# 1_-Power_Pins_Page_of_RK3399.net
KiCad netlist of a schematic drawn in Altium Designer
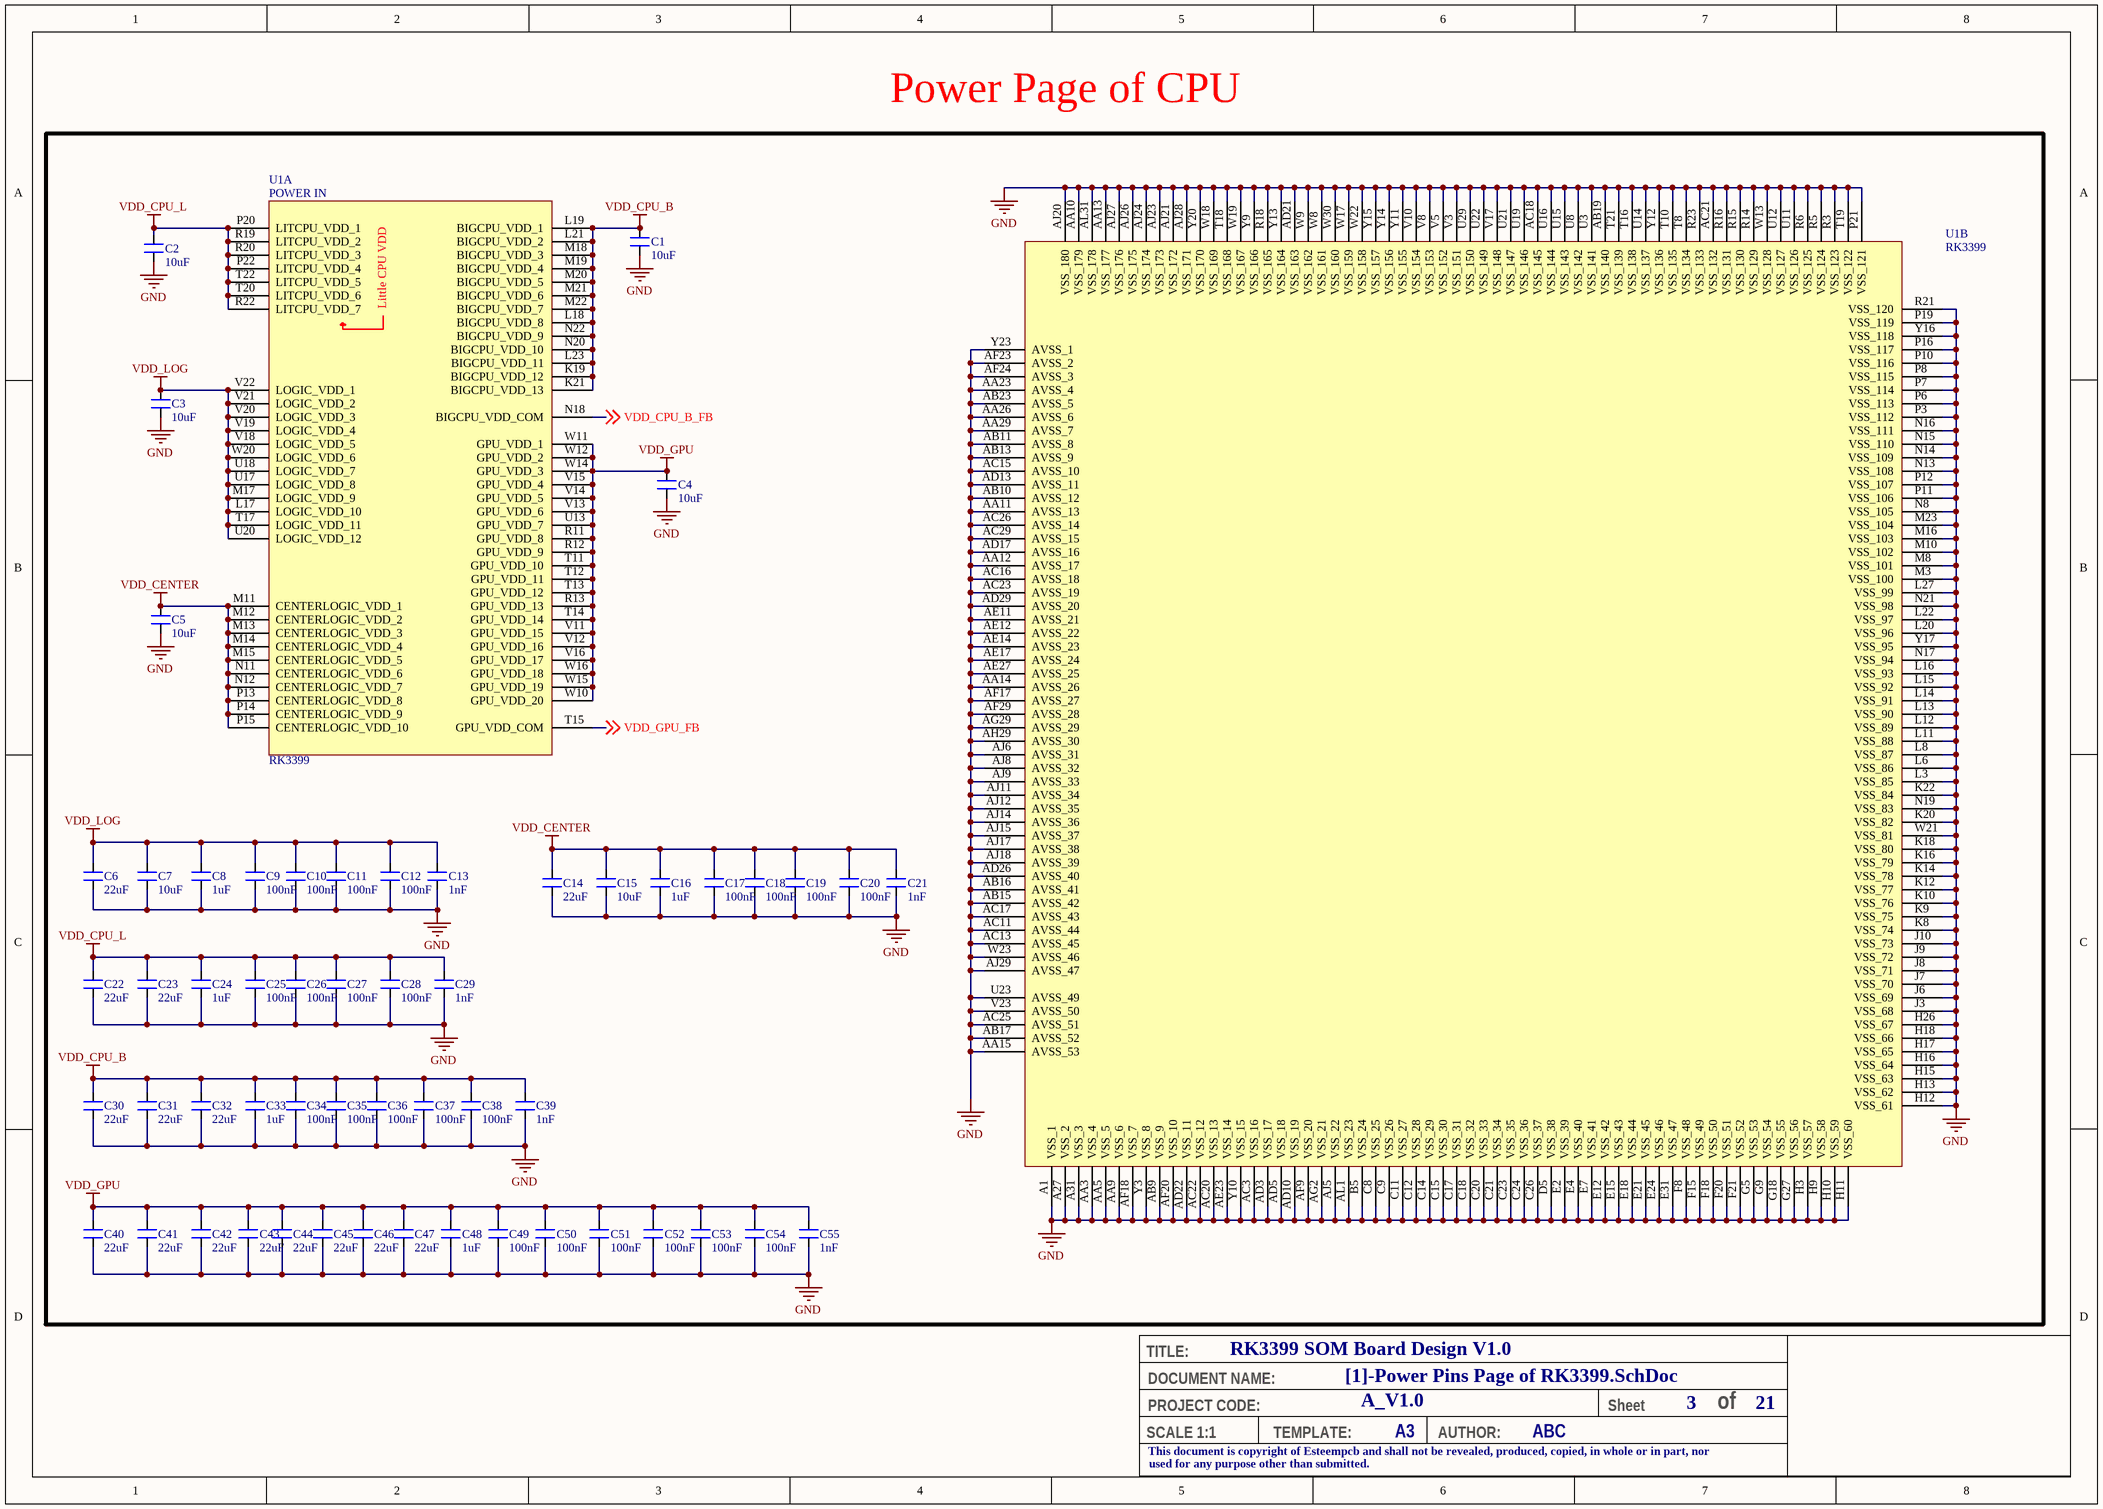
[diagram p0: [1]-Power Pins Page of RK3399.SchDoc]

(export (version "E")
  (design (tool "Eeschema 10.0.6"))
  (components
    (comp (ref "C1")
      (value "10uF")
      (footprint "CAP_0402")
      (description "10µF ±20% 10V Ceramic Capacitor X5R 0402 (1005 Metric)")
      (fields
        (field (name "MANUFACTURER PART NUMBER") "CL05A106MP5NUNC")
        (field (name "MANUFACTURER") "Samsung Electro-Mechanics")
      )
      (libsource (lib "RK3399 _Module_Schlib") (part "CAP_10uF-10V-20%-0402"))
    )
    (comp (ref "C2")
      (value "10uF")
      (footprint "CAP_0402")
      (description "10µF ±20% 10V Ceramic Capacitor X5R 0402 (1005 Metric)")
      (fields
        (field (name "MANUFACTURER PART NUMBER") "CL05A106MP5NUNC")
        (field (name "MANUFACTURER") "Samsung Electro-Mechanics")
      )
      (libsource (lib "RK3399 _Module_Schlib") (part "CAP_10uF-10V-20%-0402"))
    )
    (comp (ref "C3")
      (value "10uF")
      (footprint "CAP_0402")
      (description "10µF ±20% 10V Ceramic Capacitor X5R 0402 (1005 Metric)")
      (fields
        (field (name "MANUFACTURER PART NUMBER") "CL05A106MP5NUNC")
        (field (name "MANUFACTURER") "Samsung Electro-Mechanics")
      )
      (libsource (lib "RK3399 _Module_Schlib") (part "CAP_10uF-10V-20%-0402"))
    )
    (comp (ref "C4")
      (value "10uF")
      (footprint "CAP_0402")
      (description "10µF ±20% 10V Ceramic Capacitor X5R 0402 (1005 Metric)")
      (fields
        (field (name "MANUFACTURER PART NUMBER") "CL05A106MP5NUNC")
        (field (name "MANUFACTURER") "Samsung Electro-Mechanics")
      )
      (libsource (lib "RK3399 _Module_Schlib") (part "CAP_10uF-10V-20%-0402"))
    )
    (comp (ref "C5")
      (value "10uF")
      (footprint "CAP_0402")
      (description "10µF ±20% 10V Ceramic Capacitor X5R 0402 (1005 Metric)")
      (fields
        (field (name "MANUFACTURER PART NUMBER") "CL05A106MP5NUNC")
        (field (name "MANUFACTURER") "Samsung Electro-Mechanics")
      )
      (libsource (lib "RK3399 _Module_Schlib") (part "CAP_10uF-10V-20%-0402"))
    )
    (comp (ref "C6")
      (value "22uF")
      (footprint "CAP_0402")
      (description "22µF ±20% 6.3V Ceramic Capacitor X5R 0402 (1005 Metric)")
      (fields
        (field (name "MANUFACTURER") "Murata Electronics")
        (field (name "MANUFACTURER PART NUMBER") "CL05A226MQ5N6J8")
      )
      (libsource (lib "RK3399 _Module_Intlib") (part "CAP_22uF-6.3V-20%-0402"))
    )
    (comp (ref "C7")
      (value "10uF")
      (footprint "CAP_0402")
      (description "10µF ±20% 10V Ceramic Capacitor X5R 0402 (1005 Metric)")
      (fields
        (field (name "MANUFACTURER PART NUMBER") "CL05A106MP5NUNC")
        (field (name "MANUFACTURER") "Samsung Electro-Mechanics")
      )
      (libsource (lib "RK3399 _Module_Schlib") (part "CAP_10uF-10V-20%-0402"))
    )
    (comp (ref "C8")
      (value "1uF")
      (footprint "CAP_0201")
      (description "1µF ±20% 16V Ceramic Capacitor X5R 0201 (0603 Metric)")
      (fields
        (field (name "MANUFACTURER") "Samsung Electro-Mechanics")
        (field (name "MANUFACTURER PART NUMBER") "CL03A105MO3NRNH")
      )
      (libsource (lib "RK3399 _Module_Intlib") (part "CAP_1uF-16V-10%-0201"))
    )
    (comp (ref "C9")
      (value "100nF")
      (footprint "CAP_0201")
      (description "0.1µF ±10% 25V Ceramic Capacitor X5R 0201 (0603 Metric)")
      (fields
        (field (name "MANUFACTURER") "TDK Corporation")
        (field (name "MANUFACTURER PART NUMBER") "C0603X5R1E104K030BB")
      )
      (libsource (lib "RK3399 _Module_Intlib") (part "CAP_100nF-25V-10%-0201"))
    )
    (comp (ref "C10")
      (value "100nF")
      (footprint "CAP_0201")
      (description "0.1µF ±10% 25V Ceramic Capacitor X5R 0201 (0603 Metric)")
      (fields
        (field (name "MANUFACTURER") "TDK Corporation")
        (field (name "MANUFACTURER PART NUMBER") "C0603X5R1E104K030BB")
      )
      (libsource (lib "RK3399 _Module_Intlib") (part "CAP_100nF-25V-10%-0201"))
    )
    (comp (ref "C11")
      (value "100nF")
      (footprint "CAP_0201")
      (description "0.1µF ±10% 25V Ceramic Capacitor X5R 0201 (0603 Metric)")
      (fields
        (field (name "MANUFACTURER") "TDK Corporation")
        (field (name "MANUFACTURER PART NUMBER") "C0603X5R1E104K030BB")
      )
      (libsource (lib "RK3399 _Module_Intlib") (part "CAP_100nF-25V-10%-0201"))
    )
    (comp (ref "C12")
      (value "100nF")
      (footprint "CAP_0201")
      (description "0.1µF ±10% 25V Ceramic Capacitor X5R 0201 (0603 Metric)")
      (fields
        (field (name "MANUFACTURER") "TDK Corporation")
        (field (name "MANUFACTURER PART NUMBER") "C0603X5R1E104K030BB")
      )
      (libsource (lib "RK3399 _Module_Intlib") (part "CAP_100nF-25V-10%-0201"))
    )
    (comp (ref "C13")
      (value "1nF")
      (footprint "CAP_0201")
      (description "1000pF ±10% 16V Ceramic Capacitor X7R 0201 (0603 Metric)")
      (fields
        (field (name "MANUFACTURER") "Murata Electronics")
        (field (name "MANUFACTURER PART NUMBER") "GRM033R71C102KA01D")
      )
      (libsource (lib "RK3399 _Module_Intlib") (part "CAP_1nF-16V-10%-0201"))
    )
    (comp (ref "C14")
      (value "22uF")
      (footprint "CAP_0402")
      (description "22µF ±20% 6.3V Ceramic Capacitor X5R 0402 (1005 Metric)")
      (fields
        (field (name "MANUFACTURER") "Murata Electronics")
        (field (name "MANUFACTURER PART NUMBER") "CL05A226MQ5N6J8")
      )
      (libsource (lib "RK3399 _Module_Intlib") (part "CAP_22uF-6.3V-20%-0402"))
    )
    (comp (ref "C15")
      (value "10uF")
      (footprint "CAP_0402")
      (description "10µF ±20% 10V Ceramic Capacitor X5R 0402 (1005 Metric)")
      (fields
        (field (name "MANUFACTURER PART NUMBER") "CL05A106MP5NUNC")
        (field (name "MANUFACTURER") "Samsung Electro-Mechanics")
      )
      (libsource (lib "RK3399 _Module_Schlib") (part "CAP_10uF-10V-20%-0402"))
    )
    (comp (ref "C16")
      (value "1uF")
      (footprint "CAP_0201")
      (description "1µF ±20% 16V Ceramic Capacitor X5R 0201 (0603 Metric)")
      (fields
        (field (name "MANUFACTURER") "Samsung Electro-Mechanics")
        (field (name "MANUFACTURER PART NUMBER") "CL03A105MO3NRNH")
      )
      (libsource (lib "RK3399 _Module_Intlib") (part "CAP_1uF-16V-10%-0201"))
    )
    (comp (ref "C17")
      (value "100nF")
      (footprint "CAP_0201")
      (description "0.1µF ±10% 25V Ceramic Capacitor X5R 0201 (0603 Metric)")
      (fields
        (field (name "MANUFACTURER") "TDK Corporation")
        (field (name "MANUFACTURER PART NUMBER") "C0603X5R1E104K030BB")
      )
      (libsource (lib "RK3399 _Module_Intlib") (part "CAP_100nF-25V-10%-0201"))
    )
    (comp (ref "C18")
      (value "100nF")
      (footprint "CAP_0201")
      (description "0.1µF ±10% 25V Ceramic Capacitor X5R 0201 (0603 Metric)")
      (fields
        (field (name "MANUFACTURER") "TDK Corporation")
        (field (name "MANUFACTURER PART NUMBER") "C0603X5R1E104K030BB")
      )
      (libsource (lib "RK3399 _Module_Intlib") (part "CAP_100nF-25V-10%-0201"))
    )
    (comp (ref "C19")
      (value "100nF")
      (footprint "CAP_0201")
      (description "0.1µF ±10% 25V Ceramic Capacitor X5R 0201 (0603 Metric)")
      (fields
        (field (name "MANUFACTURER") "TDK Corporation")
        (field (name "MANUFACTURER PART NUMBER") "C0603X5R1E104K030BB")
      )
      (libsource (lib "RK3399 _Module_Intlib") (part "CAP_100nF-25V-10%-0201"))
    )
    (comp (ref "C20")
      (value "100nF")
      (footprint "CAP_0201")
      (description "0.1µF ±10% 25V Ceramic Capacitor X5R 0201 (0603 Metric)")
      (fields
        (field (name "MANUFACTURER") "TDK Corporation")
        (field (name "MANUFACTURER PART NUMBER") "C0603X5R1E104K030BB")
      )
      (libsource (lib "RK3399 _Module_Intlib") (part "CAP_100nF-25V-10%-0201"))
    )
    (comp (ref "C21")
      (value "1nF")
      (footprint "CAP_0201")
      (description "1000pF ±10% 16V Ceramic Capacitor X7R 0201 (0603 Metric)")
      (fields
        (field (name "MANUFACTURER") "Murata Electronics")
        (field (name "MANUFACTURER PART NUMBER") "GRM033R71C102KA01D")
      )
      (libsource (lib "RK3399 _Module_Intlib") (part "CAP_1nF-16V-10%-0201"))
    )
    (comp (ref "C22")
      (value "22uF")
      (footprint "CAP_0402")
      (description "22µF ±20% 6.3V Ceramic Capacitor X5R 0402 (1005 Metric)")
      (fields
        (field (name "MANUFACTURER") "Murata Electronics")
        (field (name "MANUFACTURER PART NUMBER") "CL05A226MQ5N6J8")
      )
      (libsource (lib "RK3399 _Module_Intlib") (part "CAP_22uF-6.3V-20%-0402"))
    )
    (comp (ref "C23")
      (value "22uF")
      (footprint "CAP_0402")
      (description "22µF ±20% 6.3V Ceramic Capacitor X5R 0402 (1005 Metric)")
      (fields
        (field (name "MANUFACTURER") "Murata Electronics")
        (field (name "MANUFACTURER PART NUMBER") "CL05A226MQ5N6J8")
      )
      (libsource (lib "RK3399 _Module_Intlib") (part "CAP_22uF-6.3V-20%-0402"))
    )
    (comp (ref "C24")
      (value "1uF")
      (footprint "CAP_0201")
      (description "1µF ±20% 16V Ceramic Capacitor X5R 0201 (0603 Metric)")
      (fields
        (field (name "MANUFACTURER") "Samsung Electro-Mechanics")
        (field (name "MANUFACTURER PART NUMBER") "CL03A105MO3NRNH")
      )
      (libsource (lib "RK3399 _Module_Intlib") (part "CAP_1uF-16V-10%-0201"))
    )
    (comp (ref "C25")
      (value "100nF")
      (footprint "CAP_0201")
      (description "0.1µF ±10% 25V Ceramic Capacitor X5R 0201 (0603 Metric)")
      (fields
        (field (name "MANUFACTURER") "TDK Corporation")
        (field (name "MANUFACTURER PART NUMBER") "C0603X5R1E104K030BB")
      )
      (libsource (lib "RK3399 _Module_Intlib") (part "CAP_100nF-25V-10%-0201"))
    )
    (comp (ref "C26")
      (value "100nF")
      (footprint "CAP_0201")
      (description "0.1µF ±10% 25V Ceramic Capacitor X5R 0201 (0603 Metric)")
      (fields
        (field (name "MANUFACTURER") "TDK Corporation")
        (field (name "MANUFACTURER PART NUMBER") "C0603X5R1E104K030BB")
      )
      (libsource (lib "RK3399 _Module_Intlib") (part "CAP_100nF-25V-10%-0201"))
    )
    (comp (ref "C27")
      (value "100nF")
      (footprint "CAP_0201")
      (description "0.1µF ±10% 25V Ceramic Capacitor X5R 0201 (0603 Metric)")
      (fields
        (field (name "MANUFACTURER") "TDK Corporation")
        (field (name "MANUFACTURER PART NUMBER") "C0603X5R1E104K030BB")
      )
      (libsource (lib "RK3399 _Module_Intlib") (part "CAP_100nF-25V-10%-0201"))
    )
    (comp (ref "C28")
      (value "100nF")
      (footprint "CAP_0201")
      (description "0.1µF ±10% 25V Ceramic Capacitor X5R 0201 (0603 Metric)")
      (fields
        (field (name "MANUFACTURER") "TDK Corporation")
        (field (name "MANUFACTURER PART NUMBER") "C0603X5R1E104K030BB")
      )
      (libsource (lib "RK3399 _Module_Intlib") (part "CAP_100nF-25V-10%-0201"))
    )
    (comp (ref "C29")
      (value "1nF")
      (footprint "CAP_0201")
      (description "1000pF ±10% 16V Ceramic Capacitor X7R 0201 (0603 Metric)")
      (fields
        (field (name "MANUFACTURER") "Murata Electronics")
        (field (name "MANUFACTURER PART NUMBER") "GRM033R71C102KA01D")
      )
      (libsource (lib "RK3399 _Module_Intlib") (part "CAP_1nF-16V-10%-0201"))
    )
    (comp (ref "C30")
      (value "22uF")
      (footprint "CAP_0402")
      (description "22µF ±20% 6.3V Ceramic Capacitor X5R 0402 (1005 Metric)")
      (fields
        (field (name "MANUFACTURER") "Murata Electronics")
        (field (name "MANUFACTURER PART NUMBER") "CL05A226MQ5N6J8")
      )
      (libsource (lib "RK3399 _Module_Intlib") (part "CAP_22uF-6.3V-20%-0402"))
    )
    (comp (ref "C31")
      (value "22uF")
      (footprint "CAP_0402")
      (description "22µF ±20% 6.3V Ceramic Capacitor X5R 0402 (1005 Metric)")
      (fields
        (field (name "MANUFACTURER") "Murata Electronics")
        (field (name "MANUFACTURER PART NUMBER") "CL05A226MQ5N6J8")
      )
      (libsource (lib "RK3399 _Module_Intlib") (part "CAP_22uF-6.3V-20%-0402"))
    )
    (comp (ref "C32")
      (value "22uF")
      (footprint "CAP_0402")
      (description "22µF ±20% 6.3V Ceramic Capacitor X5R 0402 (1005 Metric)")
      (fields
        (field (name "MANUFACTURER") "Murata Electronics")
        (field (name "MANUFACTURER PART NUMBER") "CL05A226MQ5N6J8")
      )
      (libsource (lib "RK3399 _Module_Intlib") (part "CAP_22uF-6.3V-20%-0402"))
    )
    (comp (ref "C33")
      (value "1uF")
      (footprint "CAP_0201")
      (description "1µF ±20% 16V Ceramic Capacitor X5R 0201 (0603 Metric)")
      (fields
        (field (name "MANUFACTURER") "Samsung Electro-Mechanics")
        (field (name "MANUFACTURER PART NUMBER") "CL03A105MO3NRNH")
      )
      (libsource (lib "RK3399 _Module_Intlib") (part "CAP_1uF-16V-10%-0201"))
    )
    (comp (ref "C34")
      (value "100nF")
      (footprint "CAP_0201")
      (description "0.1µF ±10% 25V Ceramic Capacitor X5R 0201 (0603 Metric)")
      (fields
        (field (name "MANUFACTURER") "TDK Corporation")
        (field (name "MANUFACTURER PART NUMBER") "C0603X5R1E104K030BB")
      )
      (libsource (lib "RK3399 _Module_Intlib") (part "CAP_100nF-25V-10%-0201"))
    )
    (comp (ref "C35")
      (value "100nF")
      (footprint "CAP_0201")
      (description "0.1µF ±10% 25V Ceramic Capacitor X5R 0201 (0603 Metric)")
      (fields
        (field (name "MANUFACTURER") "TDK Corporation")
        (field (name "MANUFACTURER PART NUMBER") "C0603X5R1E104K030BB")
      )
      (libsource (lib "RK3399 _Module_Intlib") (part "CAP_100nF-25V-10%-0201"))
    )
    (comp (ref "C36")
      (value "100nF")
      (footprint "CAP_0201")
      (description "0.1µF ±10% 25V Ceramic Capacitor X5R 0201 (0603 Metric)")
      (fields
        (field (name "MANUFACTURER") "TDK Corporation")
        (field (name "MANUFACTURER PART NUMBER") "C0603X5R1E104K030BB")
      )
      (libsource (lib "RK3399 _Module_Intlib") (part "CAP_100nF-25V-10%-0201"))
    )
    (comp (ref "C37")
      (value "100nF")
      (footprint "CAP_0201")
      (description "0.1µF ±10% 25V Ceramic Capacitor X5R 0201 (0603 Metric)")
      (fields
        (field (name "MANUFACTURER") "TDK Corporation")
        (field (name "MANUFACTURER PART NUMBER") "C0603X5R1E104K030BB")
      )
      (libsource (lib "RK3399 _Module_Intlib") (part "CAP_100nF-25V-10%-0201"))
    )
    (comp (ref "C38")
      (value "100nF")
      (footprint "CAP_0201")
      (description "0.1µF ±10% 25V Ceramic Capacitor X5R 0201 (0603 Metric)")
      (fields
        (field (name "MANUFACTURER") "TDK Corporation")
        (field (name "MANUFACTURER PART NUMBER") "C0603X5R1E104K030BB")
      )
      (libsource (lib "RK3399 _Module_Intlib") (part "CAP_100nF-25V-10%-0201"))
    )
    (comp (ref "C39")
      (value "1nF")
      (footprint "CAP_0201")
      (description "1000pF ±10% 16V Ceramic Capacitor X7R 0201 (0603 Metric)")
      (fields
        (field (name "MANUFACTURER") "Murata Electronics")
        (field (name "MANUFACTURER PART NUMBER") "GRM033R71C102KA01D")
      )
      (libsource (lib "RK3399 _Module_Intlib") (part "CAP_1nF-16V-10%-0201"))
    )
    (comp (ref "C40")
      (value "22uF")
      (footprint "CAP_0402")
      (description "22µF ±20% 6.3V Ceramic Capacitor X5R 0402 (1005 Metric)")
      (fields
        (field (name "MANUFACTURER") "Murata Electronics")
        (field (name "MANUFACTURER PART NUMBER") "CL05A226MQ5N6J8")
      )
      (libsource (lib "RK3399 _Module_Intlib") (part "CAP_22uF-6.3V-20%-0402"))
    )
    (comp (ref "C41")
      (value "22uF")
      (footprint "CAP_0402")
      (description "22µF ±20% 6.3V Ceramic Capacitor X5R 0402 (1005 Metric)")
      (fields
        (field (name "MANUFACTURER") "Murata Electronics")
        (field (name "MANUFACTURER PART NUMBER") "CL05A226MQ5N6J8")
      )
      (libsource (lib "RK3399 _Module_Intlib") (part "CAP_22uF-6.3V-20%-0402"))
    )
    (comp (ref "C42")
      (value "22uF")
      (footprint "CAP_0402")
      (description "22µF ±20% 6.3V Ceramic Capacitor X5R 0402 (1005 Metric)")
      (fields
        (field (name "MANUFACTURER") "Murata Electronics")
        (field (name "MANUFACTURER PART NUMBER") "CL05A226MQ5N6J8")
      )
      (libsource (lib "RK3399 _Module_Intlib") (part "CAP_22uF-6.3V-20%-0402"))
    )
    (comp (ref "C43")
      (value "22uF")
      (footprint "CAP_0402")
      (description "22µF ±20% 6.3V Ceramic Capacitor X5R 0402 (1005 Metric)")
      (fields
        (field (name "MANUFACTURER") "Murata Electronics")
        (field (name "MANUFACTURER PART NUMBER") "CL05A226MQ5N6J8")
      )
      (libsource (lib "RK3399 _Module_Intlib") (part "CAP_22uF-6.3V-20%-0402"))
    )
    (comp (ref "C44")
      (value "22uF")
      (footprint "CAP_0402")
      (description "22µF ±20% 6.3V Ceramic Capacitor X5R 0402 (1005 Metric)")
      (fields
        (field (name "MANUFACTURER") "Murata Electronics")
        (field (name "MANUFACTURER PART NUMBER") "CL05A226MQ5N6J8")
      )
      (libsource (lib "RK3399 _Module_Intlib") (part "CAP_22uF-6.3V-20%-0402"))
    )
    (comp (ref "C45")
      (value "22uF")
      (footprint "CAP_0402")
      (description "22µF ±20% 6.3V Ceramic Capacitor X5R 0402 (1005 Metric)")
      (fields
        (field (name "MANUFACTURER") "Murata Electronics")
        (field (name "MANUFACTURER PART NUMBER") "CL05A226MQ5N6J8")
      )
      (libsource (lib "RK3399 _Module_Intlib") (part "CAP_22uF-6.3V-20%-0402"))
    )
    (comp (ref "C46")
      (value "22uF")
      (footprint "CAP_0402")
      (description "22µF ±20% 6.3V Ceramic Capacitor X5R 0402 (1005 Metric)")
      (fields
        (field (name "MANUFACTURER") "Murata Electronics")
        (field (name "MANUFACTURER PART NUMBER") "CL05A226MQ5N6J8")
      )
      (libsource (lib "RK3399 _Module_Intlib") (part "CAP_22uF-6.3V-20%-0402"))
    )
    (comp (ref "C47")
      (value "22uF")
      (footprint "CAP_0402")
      (description "22µF ±20% 6.3V Ceramic Capacitor X5R 0402 (1005 Metric)")
      (fields
        (field (name "MANUFACTURER") "Murata Electronics")
        (field (name "MANUFACTURER PART NUMBER") "CL05A226MQ5N6J8")
      )
      (libsource (lib "RK3399 _Module_Intlib") (part "CAP_22uF-6.3V-20%-0402"))
    )
    (comp (ref "C48")
      (value "1uF")
      (footprint "CAP_0201")
      (description "1µF ±20% 16V Ceramic Capacitor X5R 0201 (0603 Metric)")
      (fields
        (field (name "MANUFACTURER") "Samsung Electro-Mechanics")
        (field (name "MANUFACTURER PART NUMBER") "CL03A105MO3NRNH")
      )
      (libsource (lib "RK3399 _Module_Intlib") (part "CAP_1uF-16V-10%-0201"))
    )
    (comp (ref "C49")
      (value "100nF")
      (footprint "CAP_0201")
      (description "0.1µF ±10% 25V Ceramic Capacitor X5R 0201 (0603 Metric)")
      (fields
        (field (name "MANUFACTURER") "TDK Corporation")
        (field (name "MANUFACTURER PART NUMBER") "C0603X5R1E104K030BB")
      )
      (libsource (lib "RK3399 _Module_Intlib") (part "CAP_100nF-25V-10%-0201"))
    )
    (comp (ref "C50")
      (value "100nF")
      (footprint "CAP_0201")
      (description "0.1µF ±10% 25V Ceramic Capacitor X5R 0201 (0603 Metric)")
      (fields
        (field (name "MANUFACTURER") "TDK Corporation")
        (field (name "MANUFACTURER PART NUMBER") "C0603X5R1E104K030BB")
      )
      (libsource (lib "RK3399 _Module_Intlib") (part "CAP_100nF-25V-10%-0201"))
    )
    (comp (ref "C51")
      (value "100nF")
      (footprint "CAP_0201")
      (description "0.1µF ±10% 25V Ceramic Capacitor X5R 0201 (0603 Metric)")
      (fields
        (field (name "MANUFACTURER") "TDK Corporation")
        (field (name "MANUFACTURER PART NUMBER") "C0603X5R1E104K030BB")
      )
      (libsource (lib "RK3399 _Module_Intlib") (part "CAP_100nF-25V-10%-0201"))
    )
    (comp (ref "C52")
      (value "100nF")
      (footprint "CAP_0201")
      (description "0.1µF ±10% 25V Ceramic Capacitor X5R 0201 (0603 Metric)")
      (fields
        (field (name "MANUFACTURER") "TDK Corporation")
        (field (name "MANUFACTURER PART NUMBER") "C0603X5R1E104K030BB")
      )
      (libsource (lib "RK3399 _Module_Intlib") (part "CAP_100nF-25V-10%-0201"))
    )
    (comp (ref "C53")
      (value "100nF")
      (footprint "CAP_0201")
      (description "0.1µF ±10% 25V Ceramic Capacitor X5R 0201 (0603 Metric)")
      (fields
        (field (name "MANUFACTURER") "TDK Corporation")
        (field (name "MANUFACTURER PART NUMBER") "C0603X5R1E104K030BB")
      )
      (libsource (lib "RK3399 _Module_Intlib") (part "CAP_100nF-25V-10%-0201"))
    )
    (comp (ref "C54")
      (value "100nF")
      (footprint "CAP_0201")
      (description "0.1µF ±10% 25V Ceramic Capacitor X5R 0201 (0603 Metric)")
      (fields
        (field (name "MANUFACTURER") "TDK Corporation")
        (field (name "MANUFACTURER PART NUMBER") "C0603X5R1E104K030BB")
      )
      (libsource (lib "RK3399 _Module_Intlib") (part "CAP_100nF-25V-10%-0201"))
    )
    (comp (ref "C55")
      (value "1nF")
      (footprint "CAP_0201")
      (description "1000pF ±10% 16V Ceramic Capacitor X7R 0201 (0603 Metric)")
      (fields
        (field (name "MANUFACTURER") "Murata Electronics")
        (field (name "MANUFACTURER PART NUMBER") "GRM033R71C102KA01D")
      )
      (libsource (lib "RK3399 _Module_Intlib") (part "CAP_1nF-16V-10%-0201"))
    )
    (comp (ref "U1")
      (value "RK3399")
      (footprint "FBGA828_23_826X826")
      (description "RK3399 is a low power, high performance processor for computing, personal mobile.")
      (fields (field (name "MANUFACTURER") "Rockchip"))
      (libsource (lib "RK3399 _Module_Schlib") (part "IC_RK3399-FCBGA828"))
    )
  )
  (nets
    (net (code "1") (name "GND") (class "Default")
      (node (ref "C1") (pin "1") (pinfunction "1_1") (pintype "passive"))
      (node (ref "C10") (pin "1") (pinfunction "1_1") (pintype "passive"))
      (node (ref "C11") (pin "1") (pinfunction "1_1") (pintype "passive"))
      (node (ref "C12") (pin "1") (pinfunction "1_1") (pintype "passive"))
      (node (ref "C13") (pin "1") (pinfunction "1_1") (pintype "passive"))
      (node (ref "C14") (pin "1") (pinfunction "1_1") (pintype "passive"))
      (node (ref "C15") (pin "1") (pinfunction "1_1") (pintype "passive"))
      (node (ref "C16") (pin "1") (pinfunction "1_1") (pintype "passive"))
      (node (ref "C17") (pin "1") (pinfunction "1_1") (pintype "passive"))
      (node (ref "C18") (pin "1") (pinfunction "1_1") (pintype "passive"))
      (node (ref "C19") (pin "1") (pinfunction "1_1") (pintype "passive"))
      (node (ref "C2") (pin "1") (pinfunction "1_1") (pintype "passive"))
      (node (ref "C20") (pin "1") (pinfunction "1_1") (pintype "passive"))
      (node (ref "C21") (pin "1") (pinfunction "1_1") (pintype "passive"))
      (node (ref "C22") (pin "1") (pinfunction "1_1") (pintype "passive"))
      (node (ref "C23") (pin "1") (pinfunction "1_1") (pintype "passive"))
      (node (ref "C24") (pin "1") (pinfunction "1_1") (pintype "passive"))
      (node (ref "C25") (pin "1") (pinfunction "1_1") (pintype "passive"))
      (node (ref "C26") (pin "1") (pinfunction "1_1") (pintype "passive"))
      (node (ref "C27") (pin "1") (pinfunction "1_1") (pintype "passive"))
      (node (ref "C28") (pin "1") (pinfunction "1_1") (pintype "passive"))
      (node (ref "C29") (pin "1") (pinfunction "1_1") (pintype "passive"))
      (node (ref "C3") (pin "1") (pinfunction "1_1") (pintype "passive"))
      (node (ref "C30") (pin "1") (pinfunction "1_1") (pintype "passive"))
      (node (ref "C31") (pin "1") (pinfunction "1_1") (pintype "passive"))
      (node (ref "C32") (pin "1") (pinfunction "1_1") (pintype "passive"))
      (node (ref "C33") (pin "1") (pinfunction "1_1") (pintype "passive"))
      (node (ref "C34") (pin "1") (pinfunction "1_1") (pintype "passive"))
      (node (ref "C35") (pin "1") (pinfunction "1_1") (pintype "passive"))
      (node (ref "C36") (pin "1") (pinfunction "1_1") (pintype "passive"))
      (node (ref "C37") (pin "1") (pinfunction "1_1") (pintype "passive"))
      (node (ref "C38") (pin "1") (pinfunction "1_1") (pintype "passive"))
      (node (ref "C39") (pin "1") (pinfunction "1_1") (pintype "passive"))
      (node (ref "C4") (pin "1") (pinfunction "1_1") (pintype "passive"))
      (node (ref "C40") (pin "1") (pinfunction "1_1") (pintype "passive"))
      (node (ref "C41") (pin "1") (pinfunction "1_1") (pintype "passive"))
      (node (ref "C42") (pin "1") (pinfunction "1_1") (pintype "passive"))
      (node (ref "C43") (pin "1") (pinfunction "1_1") (pintype "passive"))
      (node (ref "C44") (pin "1") (pinfunction "1_1") (pintype "passive"))
      (node (ref "C45") (pin "1") (pinfunction "1_1") (pintype "passive"))
      (node (ref "C46") (pin "1") (pinfunction "1_1") (pintype "passive"))
      (node (ref "C47") (pin "1") (pinfunction "1_1") (pintype "passive"))
      (node (ref "C48") (pin "1") (pinfunction "1_1") (pintype "passive"))
      (node (ref "C49") (pin "1") (pinfunction "1_1") (pintype "passive"))
      (node (ref "C5") (pin "1") (pinfunction "1_1") (pintype "passive"))
      (node (ref "C50") (pin "1") (pinfunction "1_1") (pintype "passive"))
      (node (ref "C51") (pin "1") (pinfunction "1_1") (pintype "passive"))
      (node (ref "C52") (pin "1") (pinfunction "1_1") (pintype "passive"))
      (node (ref "C53") (pin "1") (pinfunction "1_1") (pintype "passive"))
      (node (ref "C54") (pin "1") (pinfunction "1_1") (pintype "passive"))
      (node (ref "C55") (pin "1") (pinfunction "1_1") (pintype "passive"))
      (node (ref "C6") (pin "1") (pinfunction "1_1") (pintype "passive"))
      (node (ref "C7") (pin "1") (pinfunction "1_1") (pintype "passive"))
      (node (ref "C8") (pin "1") (pinfunction "1_1") (pintype "passive"))
      (node (ref "C9") (pin "1") (pinfunction "1_1") (pintype "passive"))
      (node (ref "U1") (pin "A1") (pinfunction "VSS_1_A1") (pintype "passive"))
      (node (ref "U1") (pin "A27") (pinfunction "VSS_2_A27") (pintype "passive"))
      (node (ref "U1") (pin "A31") (pinfunction "VSS_3_A31") (pintype "passive"))
      (node (ref "U1") (pin "AA10") (pinfunction "VSS_179_AA10") (pintype "passive"))
      (node (ref "U1") (pin "AA11") (pinfunction "AVSS_13_AA11") (pintype "passive"))
      (node (ref "U1") (pin "AA12") (pinfunction "AVSS_17_AA12") (pintype "passive"))
      (node (ref "U1") (pin "AA13") (pinfunction "VSS_177_AA13") (pintype "passive"))
      (node (ref "U1") (pin "AA14") (pinfunction "AVSS_26_AA14") (pintype "passive"))
      (node (ref "U1") (pin "AA15") (pinfunction "AVSS_53_AA15") (pintype "passive"))
      (node (ref "U1") (pin "AA23") (pinfunction "AVSS_4_AA23") (pintype "passive"))
      (node (ref "U1") (pin "AA26") (pinfunction "AVSS_6_AA26") (pintype "passive"))
      (node (ref "U1") (pin "AA29") (pinfunction "AVSS_7_AA29") (pintype "passive"))
      (node (ref "U1") (pin "AA3") (pinfunction "VSS_4_AA3") (pintype "passive"))
      (node (ref "U1") (pin "AA5") (pinfunction "VSS_5_AA5") (pintype "passive"))
      (node (ref "U1") (pin "AA9") (pinfunction "VSS_6_AA9") (pintype "passive"))
      (node (ref "U1") (pin "AB10") (pinfunction "AVSS_12_AB10") (pintype "passive"))
      (node (ref "U1") (pin "AB11") (pinfunction "AVSS_8_AB11") (pintype "passive"))
      (node (ref "U1") (pin "AB13") (pinfunction "AVSS_9_AB13") (pintype "passive"))
      (node (ref "U1") (pin "AB15") (pinfunction "AVSS_42_AB15") (pintype "passive"))
      (node (ref "U1") (pin "AB16") (pinfunction "AVSS_41_AB16") (pintype "passive"))
      (node (ref "U1") (pin "AB17") (pinfunction "AVSS_52_AB17") (pintype "passive"))
      (node (ref "U1") (pin "AB19") (pinfunction "VSS_140_AB19") (pintype "passive"))
      (node (ref "U1") (pin "AB23") (pinfunction "AVSS_5_AB23") (pintype "passive"))
      (node (ref "U1") (pin "AB9") (pinfunction "VSS_9_AB9") (pintype "passive"))
      (node (ref "U1") (pin "AC11") (pinfunction "AVSS_44_AC11") (pintype "passive"))
      (node (ref "U1") (pin "AC13") (pinfunction "AVSS_45_AC13") (pintype "passive"))
      (node (ref "U1") (pin "AC15") (pinfunction "AVSS_10_AC15") (pintype "passive"))
      (node (ref "U1") (pin "AC16") (pinfunction "AVSS_18_AC16") (pintype "passive"))
      (node (ref "U1") (pin "AC17") (pinfunction "AVSS_43_AC17") (pintype "passive"))
      (node (ref "U1") (pin "AC18") (pinfunction "VSS_145_AC18") (pintype "passive"))
      (node (ref "U1") (pin "AC20") (pinfunction "VSS_13_AC20") (pintype "passive"))
      (node (ref "U1") (pin "AC21") (pinfunction "VSS_132_AC21") (pintype "passive"))
      (node (ref "U1") (pin "AC22") (pinfunction "VSS_12_AC22") (pintype "passive"))
      (node (ref "U1") (pin "AC23") (pinfunction "AVSS_19_AC23") (pintype "passive"))
      (node (ref "U1") (pin "AC25") (pinfunction "AVSS_51_AC25") (pintype "passive"))
      (node (ref "U1") (pin "AC26") (pinfunction "AVSS_14_AC26") (pintype "passive"))
      (node (ref "U1") (pin "AC29") (pinfunction "AVSS_15_AC29") (pintype "passive"))
      (node (ref "U1") (pin "AC3") (pinfunction "VSS_16_AC3") (pintype "passive"))
      (node (ref "U1") (pin "AD10") (pinfunction "VSS_19_AD10") (pintype "passive"))
      (node (ref "U1") (pin "AD13") (pinfunction "AVSS_11_AD13") (pintype "passive"))
      (node (ref "U1") (pin "AD17") (pinfunction "AVSS_16_AD17") (pintype "passive"))
      (node (ref "U1") (pin "AD21") (pinfunction "VSS_163_AD21") (pintype "passive"))
      (node (ref "U1") (pin "AD22") (pinfunction "VSS_11_AD22") (pintype "passive"))
      (node (ref "U1") (pin "AD26") (pinfunction "AVSS_40_AD26") (pintype "passive"))
      (node (ref "U1") (pin "AD29") (pinfunction "AVSS_20_AD29") (pintype "passive"))
      (node (ref "U1") (pin "AD3") (pinfunction "VSS_17_AD3") (pintype "passive"))
      (node (ref "U1") (pin "AD5") (pinfunction "VSS_18_AD5") (pintype "passive"))
      (node (ref "U1") (pin "AE11") (pinfunction "AVSS_21_AE11") (pintype "passive"))
      (node (ref "U1") (pin "AE12") (pinfunction "AVSS_22_AE12") (pintype "passive"))
      (node (ref "U1") (pin "AE14") (pinfunction "AVSS_23_AE14") (pintype "passive"))
      (node (ref "U1") (pin "AE17") (pinfunction "AVSS_24_AE17") (pintype "passive"))
      (node (ref "U1") (pin "AE23") (pinfunction "VSS_14_AE23") (pintype "passive"))
      (node (ref "U1") (pin "AE27") (pinfunction "AVSS_25_AE27") (pintype "passive"))
      (node (ref "U1") (pin "AF17") (pinfunction "AVSS_27_AF17") (pintype "passive"))
      (node (ref "U1") (pin "AF18") (pinfunction "VSS_7_AF18") (pintype "passive"))
      (node (ref "U1") (pin "AF20") (pinfunction "VSS_10_AF20") (pintype "passive"))
      (node (ref "U1") (pin "AF23") (pinfunction "AVSS_2_AF23") (pintype "passive"))
      (node (ref "U1") (pin "AF24") (pinfunction "AVSS_3_AF24") (pintype "passive"))
      (node (ref "U1") (pin "AF29") (pinfunction "AVSS_28_AF29") (pintype "passive"))
      (node (ref "U1") (pin "AF9") (pinfunction "VSS_20_AF9") (pintype "passive"))
      (node (ref "U1") (pin "AG2") (pinfunction "VSS_21_AG2") (pintype "passive"))
      (node (ref "U1") (pin "AG29") (pinfunction "AVSS_29_AG29") (pintype "passive"))
      (node (ref "U1") (pin "AH29") (pinfunction "AVSS_30_AH29") (pintype "passive"))
      (node (ref "U1") (pin "AJ11") (pinfunction "AVSS_34_AJ11") (pintype "passive"))
      (node (ref "U1") (pin "AJ12") (pinfunction "AVSS_35_AJ12") (pintype "passive"))
      (node (ref "U1") (pin "AJ14") (pinfunction "AVSS_36_AJ14") (pintype "passive"))
      (node (ref "U1") (pin "AJ15") (pinfunction "AVSS_37_AJ15") (pintype "passive"))
      (node (ref "U1") (pin "AJ17") (pinfunction "AVSS_38_AJ17") (pintype "passive"))
      (node (ref "U1") (pin "AJ18") (pinfunction "AVSS_39_AJ18") (pintype "passive"))
      (node (ref "U1") (pin "AJ20") (pinfunction "VSS_180_AJ20") (pintype "passive"))
      (node (ref "U1") (pin "AJ21") (pinfunction "VSS_172_AJ21") (pintype "passive"))
      (node (ref "U1") (pin "AJ23") (pinfunction "VSS_173_AJ23") (pintype "passive"))
      (node (ref "U1") (pin "AJ24") (pinfunction "VSS_174_AJ24") (pintype "passive"))
      (node (ref "U1") (pin "AJ26") (pinfunction "VSS_175_AJ26") (pintype "passive"))
      (node (ref "U1") (pin "AJ27") (pinfunction "VSS_176_AJ27") (pintype "passive"))
      (node (ref "U1") (pin "AJ28") (pinfunction "VSS_171_AJ28") (pintype "passive"))
      (node (ref "U1") (pin "AJ29") (pinfunction "AVSS_47_AJ29") (pintype "passive"))
      (node (ref "U1") (pin "AJ5") (pinfunction "VSS_22_AJ5") (pintype "passive"))
      (node (ref "U1") (pin "AJ6") (pinfunction "AVSS_31_AJ6") (pintype "passive"))
      (node (ref "U1") (pin "AJ8") (pinfunction "AVSS_32_AJ8") (pintype "passive"))
      (node (ref "U1") (pin "AJ9") (pinfunction "AVSS_33_AJ9") (pintype "passive"))
      (node (ref "U1") (pin "AL1") (pinfunction "VSS_23_AL1") (pintype "passive"))
      (node (ref "U1") (pin "AL31") (pinfunction "VSS_178_AL31") (pintype "passive"))
      (node (ref "U1") (pin "B5") (pinfunction "VSS_24_B5") (pintype "passive"))
      (node (ref "U1") (pin "C11") (pinfunction "VSS_27_C11") (pintype "passive"))
      (node (ref "U1") (pin "C12") (pinfunction "VSS_28_C12") (pintype "passive"))
      (node (ref "U1") (pin "C14") (pinfunction "VSS_29_C14") (pintype "passive"))
      (node (ref "U1") (pin "C15") (pinfunction "VSS_30_C15") (pintype "passive"))
      (node (ref "U1") (pin "C17") (pinfunction "VSS_31_C17") (pintype "passive"))
      (node (ref "U1") (pin "C18") (pinfunction "VSS_32_C18") (pintype "passive"))
      (node (ref "U1") (pin "C20") (pinfunction "VSS_33_C20") (pintype "passive"))
      (node (ref "U1") (pin "C21") (pinfunction "VSS_34_C21") (pintype "passive"))
      (node (ref "U1") (pin "C23") (pinfunction "VSS_35_C23") (pintype "passive"))
      (node (ref "U1") (pin "C24") (pinfunction "VSS_36_C24") (pintype "passive"))
      (node (ref "U1") (pin "C26") (pinfunction "VSS_37_C26") (pintype "passive"))
      (node (ref "U1") (pin "C8") (pinfunction "VSS_25_C8") (pintype "passive"))
      (node (ref "U1") (pin "C9") (pinfunction "VSS_26_C9") (pintype "passive"))
      (node (ref "U1") (pin "D5") (pinfunction "VSS_38_D5") (pintype "passive"))
      (node (ref "U1") (pin "E12") (pinfunction "VSS_42_E12") (pintype "passive"))
      (node (ref "U1") (pin "E15") (pinfunction "VSS_43_E15") (pintype "passive"))
      (node (ref "U1") (pin "E18") (pinfunction "VSS_44_E18") (pintype "passive"))
      (node (ref "U1") (pin "E2") (pinfunction "VSS_39_E2") (pintype "passive"))
      (node (ref "U1") (pin "E21") (pinfunction "VSS_45_E21") (pintype "passive"))
      (node (ref "U1") (pin "E24") (pinfunction "VSS_46_E24") (pintype "passive"))
      (node (ref "U1") (pin "E31") (pinfunction "VSS_47_E31") (pintype "passive"))
      (node (ref "U1") (pin "E4") (pinfunction "VSS_40_E4") (pintype "passive"))
      (node (ref "U1") (pin "E7") (pinfunction "VSS_41_E7") (pintype "passive"))
      (node (ref "U1") (pin "F15") (pinfunction "VSS_49_F15") (pintype "passive"))
      (node (ref "U1") (pin "F18") (pinfunction "VSS_50_F18") (pintype "passive"))
      (node (ref "U1") (pin "F20") (pinfunction "VSS_51_F20") (pintype "passive"))
      (node (ref "U1") (pin "F21") (pinfunction "VSS_52_F21") (pintype "passive"))
      (node (ref "U1") (pin "F8") (pinfunction "VSS_48_F8") (pintype "passive"))
      (node (ref "U1") (pin "G18") (pinfunction "VSS_55_G18") (pintype "passive"))
      (node (ref "U1") (pin "G27") (pinfunction "VSS_56_G27") (pintype "passive"))
      (node (ref "U1") (pin "G5") (pinfunction "VSS_53_G5") (pintype "passive"))
      (node (ref "U1") (pin "G9") (pinfunction "VSS_54_G9") (pintype "passive"))
      (node (ref "U1") (pin "H10") (pinfunction "VSS_59_H10") (pintype "passive"))
      (node (ref "U1") (pin "H11") (pinfunction "VSS_60_H11") (pintype "passive"))
      (node (ref "U1") (pin "H12") (pinfunction "VSS_61_H12") (pintype "passive"))
      (node (ref "U1") (pin "H13") (pinfunction "VSS_62_H13") (pintype "passive"))
      (node (ref "U1") (pin "H15") (pinfunction "VSS_63_H15") (pintype "passive"))
      (node (ref "U1") (pin "H16") (pinfunction "VSS_64_H16") (pintype "passive"))
      (node (ref "U1") (pin "H17") (pinfunction "VSS_65_H17") (pintype "passive"))
      (node (ref "U1") (pin "H18") (pinfunction "VSS_66_H18") (pintype "passive"))
      (node (ref "U1") (pin "H26") (pinfunction "VSS_67_H26") (pintype "passive"))
      (node (ref "U1") (pin "H3") (pinfunction "VSS_57_H3") (pintype "passive"))
      (node (ref "U1") (pin "H9") (pinfunction "VSS_58_H9") (pintype "passive"))
      (node (ref "U1") (pin "J10") (pinfunction "VSS_73_J10") (pintype "passive"))
      (node (ref "U1") (pin "J3") (pinfunction "VSS_68_J3") (pintype "passive"))
      (node (ref "U1") (pin "J6") (pinfunction "VSS_69_J6") (pintype "passive"))
      (node (ref "U1") (pin "J7") (pinfunction "VSS_70_J7") (pintype "passive"))
      (node (ref "U1") (pin "J8") (pinfunction "VSS_71_J8") (pintype "passive"))
      (node (ref "U1") (pin "J9") (pinfunction "VSS_72_J9") (pintype "passive"))
      (node (ref "U1") (pin "K10") (pinfunction "VSS_76_K10") (pintype "passive"))
      (node (ref "U1") (pin "K12") (pinfunction "VSS_77_K12") (pintype "passive"))
      (node (ref "U1") (pin "K14") (pinfunction "VSS_78_K14") (pintype "passive"))
      (node (ref "U1") (pin "K16") (pinfunction "VSS_79_K16") (pintype "passive"))
      (node (ref "U1") (pin "K18") (pinfunction "VSS_80_K18") (pintype "passive"))
      (node (ref "U1") (pin "K20") (pinfunction "VSS_82_K20") (pintype "passive"))
      (node (ref "U1") (pin "K22") (pinfunction "VSS_84_K22") (pintype "passive"))
      (node (ref "U1") (pin "K8") (pinfunction "VSS_74_K8") (pintype "passive"))
      (node (ref "U1") (pin "K9") (pinfunction "VSS_75_K9") (pintype "passive"))
      (node (ref "U1") (pin "L11") (pinfunction "VSS_88_L11") (pintype "passive"))
      (node (ref "U1") (pin "L12") (pinfunction "VSS_89_L12") (pintype "passive"))
      (node (ref "U1") (pin "L13") (pinfunction "VSS_90_L13") (pintype "passive"))
      (node (ref "U1") (pin "L14") (pinfunction "VSS_91_L14") (pintype "passive"))
      (node (ref "U1") (pin "L15") (pinfunction "VSS_92_L15") (pintype "passive"))
      (node (ref "U1") (pin "L16") (pinfunction "VSS_93_L16") (pintype "passive"))
      (node (ref "U1") (pin "L20") (pinfunction "VSS_96_L20") (pintype "passive"))
      (node (ref "U1") (pin "L22") (pinfunction "VSS_97_L22") (pintype "passive"))
      (node (ref "U1") (pin "L27") (pinfunction "VSS_99_L27") (pintype "passive"))
      (node (ref "U1") (pin "L3") (pinfunction "VSS_85_L3") (pintype "passive"))
      (node (ref "U1") (pin "L6") (pinfunction "VSS_86_L6") (pintype "passive"))
      (node (ref "U1") (pin "L8") (pinfunction "VSS_87_L8") (pintype "passive"))
      (node (ref "U1") (pin "M10") (pinfunction "VSS_102_M10") (pintype "passive"))
      (node (ref "U1") (pin "M16") (pinfunction "VSS_103_M16") (pintype "passive"))
      (node (ref "U1") (pin "M23") (pinfunction "VSS_104_M23") (pintype "passive"))
      (node (ref "U1") (pin "M3") (pinfunction "VSS_100_M3") (pintype "passive"))
      (node (ref "U1") (pin "M8") (pinfunction "VSS_101_M8") (pintype "passive"))
      (node (ref "U1") (pin "N13") (pinfunction "VSS_108_N13") (pintype "passive"))
      (node (ref "U1") (pin "N14") (pinfunction "VSS_109_N14") (pintype "passive"))
      (node (ref "U1") (pin "N15") (pinfunction "VSS_110_N15") (pintype "passive"))
      (node (ref "U1") (pin "N16") (pinfunction "VSS_111_N16") (pintype "passive"))
      (node (ref "U1") (pin "N17") (pinfunction "VSS_94_N17") (pintype "passive"))
      (node (ref "U1") (pin "N19") (pinfunction "VSS_83_N19") (pintype "passive"))
      (node (ref "U1") (pin "N21") (pinfunction "VSS_98_N21") (pintype "passive"))
      (node (ref "U1") (pin "N8") (pinfunction "VSS_105_N8") (pintype "passive"))
      (node (ref "U1") (pin "P10") (pinfunction "VSS_116_P10") (pintype "passive"))
      (node (ref "U1") (pin "P11") (pinfunction "VSS_106_P11") (pintype "passive"))
      (node (ref "U1") (pin "P12") (pinfunction "VSS_107_P12") (pintype "passive"))
      (node (ref "U1") (pin "P16") (pinfunction "VSS_117_P16") (pintype "passive"))
      (node (ref "U1") (pin "P19") (pinfunction "VSS_119_P19") (pintype "passive"))
      (node (ref "U1") (pin "P21") (pinfunction "VSS_121_P21") (pintype "passive"))
      (node (ref "U1") (pin "P3") (pinfunction "VSS_112_P3") (pintype "passive"))
      (node (ref "U1") (pin "P6") (pinfunction "VSS_113_P6") (pintype "passive"))
      (node (ref "U1") (pin "P7") (pinfunction "VSS_114_P7") (pintype "passive"))
      (node (ref "U1") (pin "P8") (pinfunction "VSS_115_P8") (pintype "passive"))
      (node (ref "U1") (pin "R14") (pinfunction "VSS_129_R14") (pintype "passive"))
      (node (ref "U1") (pin "R15") (pinfunction "VSS_130_R15") (pintype "passive"))
      (node (ref "U1") (pin "R16") (pinfunction "VSS_131_R16") (pintype "passive"))
      (node (ref "U1") (pin "R18") (pinfunction "VSS_165_R18") (pintype "passive"))
      (node (ref "U1") (pin "R21") (pinfunction "VSS_120_R21") (pintype "passive"))
      (node (ref "U1") (pin "R23") (pinfunction "VSS_133_R23") (pintype "passive"))
      (node (ref "U1") (pin "R3") (pinfunction "VSS_123_R3") (pintype "passive"))
      (node (ref "U1") (pin "R5") (pinfunction "VSS_124_R5") (pintype "passive"))
      (node (ref "U1") (pin "R6") (pinfunction "VSS_125_R6") (pintype "passive"))
      (node (ref "U1") (pin "T10") (pinfunction "VSS_135_T10") (pintype "passive"))
      (node (ref "U1") (pin "T16") (pinfunction "VSS_138_T16") (pintype "passive"))
      (node (ref "U1") (pin "T18") (pinfunction "VSS_168_T18") (pintype "passive"))
      (node (ref "U1") (pin "T19") (pinfunction "VSS_122_T19") (pintype "passive"))
      (node (ref "U1") (pin "T21") (pinfunction "VSS_139_T21") (pintype "passive"))
      (node (ref "U1") (pin "T8") (pinfunction "VSS_134_T8") (pintype "passive"))
      (node (ref "U1") (pin "U11") (pinfunction "VSS_126_U11") (pintype "passive"))
      (node (ref "U1") (pin "U12") (pinfunction "VSS_127_U12") (pintype "passive"))
      (node (ref "U1") (pin "U14") (pinfunction "VSS_137_U14") (pintype "passive"))
      (node (ref "U1") (pin "U15") (pinfunction "VSS_143_U15") (pintype "passive"))
      (node (ref "U1") (pin "U16") (pinfunction "VSS_144_U16") (pintype "passive"))
      (node (ref "U1") (pin "U19") (pinfunction "VSS_146_U19") (pintype "passive"))
      (node (ref "U1") (pin "U21") (pinfunction "VSS_147_U21") (pintype "passive"))
      (node (ref "U1") (pin "U22") (pinfunction "VSS_149_U22") (pintype "passive"))
      (node (ref "U1") (pin "U23") (pinfunction "AVSS_49_U23") (pintype "passive"))
      (node (ref "U1") (pin "U29") (pinfunction "VSS_150_U29") (pintype "passive"))
      (node (ref "U1") (pin "U3") (pinfunction "VSS_141_U3") (pintype "passive"))
      (node (ref "U1") (pin "U8") (pinfunction "VSS_142_U8") (pintype "passive"))
      (node (ref "U1") (pin "V10") (pinfunction "VSS_154_V10") (pintype "passive"))
      (node (ref "U1") (pin "V17") (pinfunction "VSS_148_V17") (pintype "passive"))
      (node (ref "U1") (pin "V23") (pinfunction "AVSS_50_V23") (pintype "passive"))
      (node (ref "U1") (pin "V3") (pinfunction "VSS_151_V3") (pintype "passive"))
      (node (ref "U1") (pin "V5") (pinfunction "VSS_152_V5") (pintype "passive"))
      (node (ref "U1") (pin "V8") (pinfunction "VSS_153_V8") (pintype "passive"))
      (node (ref "U1") (pin "W13") (pinfunction "VSS_128_W13") (pintype "passive"))
      (node (ref "U1") (pin "W17") (pinfunction "VSS_159_W17") (pintype "passive"))
      (node (ref "U1") (pin "W18") (pinfunction "VSS_169_W18") (pintype "passive"))
      (node (ref "U1") (pin "W19") (pinfunction "VSS_167_W19") (pintype "passive"))
      (node (ref "U1") (pin "W21") (pinfunction "VSS_81_W21") (pintype "passive"))
      (node (ref "U1") (pin "W22") (pinfunction "VSS_158_W22") (pintype "passive"))
      (node (ref "U1") (pin "W23") (pinfunction "AVSS_46_W23") (pintype "passive"))
      (node (ref "U1") (pin "W30") (pinfunction "VSS_160_W30") (pintype "passive"))
      (node (ref "U1") (pin "W8") (pinfunction "VSS_161_W8") (pintype "passive"))
      (node (ref "U1") (pin "W9") (pinfunction "VSS_162_W9") (pintype "passive"))
      (node (ref "U1") (pin "Y10") (pinfunction "VSS_15_Y10") (pintype "passive"))
      (node (ref "U1") (pin "Y11") (pinfunction "VSS_155_Y11") (pintype "passive"))
      (node (ref "U1") (pin "Y12") (pinfunction "VSS_136_Y12") (pintype "passive"))
      (node (ref "U1") (pin "Y13") (pinfunction "VSS_164_Y13") (pintype "passive"))
      (node (ref "U1") (pin "Y14") (pinfunction "VSS_156_Y14") (pintype "passive"))
      (node (ref "U1") (pin "Y15") (pinfunction "VSS_157_Y15") (pintype "passive"))
      (node (ref "U1") (pin "Y16") (pinfunction "VSS_118_Y16") (pintype "passive"))
      (node (ref "U1") (pin "Y17") (pinfunction "VSS_95_Y17") (pintype "passive"))
      (node (ref "U1") (pin "Y20") (pinfunction "VSS_170_Y20") (pintype "passive"))
      (node (ref "U1") (pin "Y23") (pinfunction "AVSS_1_Y23") (pintype "passive"))
      (node (ref "U1") (pin "Y3") (pinfunction "VSS_8_Y3") (pintype "passive"))
      (node (ref "U1") (pin "Y9") (pinfunction "VSS_166_Y9") (pintype "passive"))
    )
    (net (code "2") (name "VDD_CENTER") (class "Default")
      (node (ref "C14") (pin "2") (pinfunction "2_2") (pintype "passive"))
      (node (ref "C15") (pin "2") (pinfunction "2_2") (pintype "passive"))
      (node (ref "C16") (pin "2") (pinfunction "2_2") (pintype "passive"))
      (node (ref "C17") (pin "2") (pinfunction "2_2") (pintype "passive"))
      (node (ref "C18") (pin "2") (pinfunction "2_2") (pintype "passive"))
      (node (ref "C19") (pin "2") (pinfunction "2_2") (pintype "passive"))
      (node (ref "C20") (pin "2") (pinfunction "2_2") (pintype "passive"))
      (node (ref "C21") (pin "2") (pinfunction "2_2") (pintype "passive"))
      (node (ref "C5") (pin "2") (pinfunction "2_2") (pintype "passive"))
      (node (ref "U1") (pin "M11") (pinfunction "CENTERLOGIC_VDD_1_M11") (pintype "passive"))
      (node (ref "U1") (pin "M12") (pinfunction "CENTERLOGIC_VDD_2_M12") (pintype "passive"))
      (node (ref "U1") (pin "M13") (pinfunction "CENTERLOGIC_VDD_3_M13") (pintype "passive"))
      (node (ref "U1") (pin "M14") (pinfunction "CENTERLOGIC_VDD_4_M14") (pintype "passive"))
      (node (ref "U1") (pin "M15") (pinfunction "CENTERLOGIC_VDD_5_M15") (pintype "passive"))
      (node (ref "U1") (pin "N11") (pinfunction "CENTERLOGIC_VDD_6_N11") (pintype "passive"))
      (node (ref "U1") (pin "N12") (pinfunction "CENTERLOGIC_VDD_7_N12") (pintype "passive"))
      (node (ref "U1") (pin "P13") (pinfunction "CENTERLOGIC_VDD_8_P13") (pintype "passive"))
      (node (ref "U1") (pin "P14") (pinfunction "CENTERLOGIC_VDD_9_P14") (pintype "passive"))
      (node (ref "U1") (pin "P15") (pinfunction "CENTERLOGIC_VDD_10_P15") (pintype "passive"))
    )
    (net (code "3") (name "VDD_CPU_B") (class "Default")
      (node (ref "C1") (pin "2") (pinfunction "2_2") (pintype "passive"))
      (node (ref "C30") (pin "2") (pinfunction "2_2") (pintype "passive"))
      (node (ref "C31") (pin "2") (pinfunction "2_2") (pintype "passive"))
      (node (ref "C32") (pin "2") (pinfunction "2_2") (pintype "passive"))
      (node (ref "C33") (pin "2") (pinfunction "2_2") (pintype "passive"))
      (node (ref "C34") (pin "2") (pinfunction "2_2") (pintype "passive"))
      (node (ref "C35") (pin "2") (pinfunction "2_2") (pintype "passive"))
      (node (ref "C36") (pin "2") (pinfunction "2_2") (pintype "passive"))
      (node (ref "C37") (pin "2") (pinfunction "2_2") (pintype "passive"))
      (node (ref "C38") (pin "2") (pinfunction "2_2") (pintype "passive"))
      (node (ref "C39") (pin "2") (pinfunction "2_2") (pintype "passive"))
      (node (ref "U1") (pin "K19") (pinfunction "BIGCPU_VDD_12_K19") (pintype "passive"))
      (node (ref "U1") (pin "K21") (pinfunction "BIGCPU_VDD_13_K21") (pintype "passive"))
      (node (ref "U1") (pin "L18") (pinfunction "BIGCPU_VDD_8_L18") (pintype "passive"))
      (node (ref "U1") (pin "L19") (pinfunction "BIGCPU_VDD_1_L19") (pintype "passive"))
      (node (ref "U1") (pin "L21") (pinfunction "BIGCPU_VDD_2_L21") (pintype "passive"))
      (node (ref "U1") (pin "L23") (pinfunction "BIGCPU_VDD_11_L23") (pintype "passive"))
      (node (ref "U1") (pin "M18") (pinfunction "BIGCPU_VDD_3_M18") (pintype "passive"))
      (node (ref "U1") (pin "M19") (pinfunction "BIGCPU_VDD_4_M19") (pintype "passive"))
      (node (ref "U1") (pin "M20") (pinfunction "BIGCPU_VDD_5_M20") (pintype "passive"))
      (node (ref "U1") (pin "M21") (pinfunction "BIGCPU_VDD_6_M21") (pintype "passive"))
      (node (ref "U1") (pin "M22") (pinfunction "BIGCPU_VDD_7_M22") (pintype "passive"))
      (node (ref "U1") (pin "N20") (pinfunction "BIGCPU_VDD_10_N20") (pintype "passive"))
      (node (ref "U1") (pin "N22") (pinfunction "BIGCPU_VDD_9_N22") (pintype "passive"))
    )
    (net (code "4") (name "VDD_CPU_B_FB") (class "Default")
      (node (ref "U1") (pin "N18") (pinfunction "BIGCPU_VDD_COM_N18") (pintype "passive"))
    )
    (net (code "5") (name "VDD_CPU_L") (class "Default")
      (node (ref "C2") (pin "2") (pinfunction "2_2") (pintype "passive"))
      (node (ref "C22") (pin "2") (pinfunction "2_2") (pintype "passive"))
      (node (ref "C23") (pin "2") (pinfunction "2_2") (pintype "passive"))
      (node (ref "C24") (pin "2") (pinfunction "2_2") (pintype "passive"))
      (node (ref "C25") (pin "2") (pinfunction "2_2") (pintype "passive"))
      (node (ref "C26") (pin "2") (pinfunction "2_2") (pintype "passive"))
      (node (ref "C27") (pin "2") (pinfunction "2_2") (pintype "passive"))
      (node (ref "C28") (pin "2") (pinfunction "2_2") (pintype "passive"))
      (node (ref "C29") (pin "2") (pinfunction "2_2") (pintype "passive"))
      (node (ref "U1") (pin "P20") (pinfunction "LITCPU_VDD_1_P20") (pintype "passive"))
      (node (ref "U1") (pin "P22") (pinfunction "LITCPU_VDD_4_P22") (pintype "passive"))
      (node (ref "U1") (pin "R19") (pinfunction "LITCPU_VDD_2_R19") (pintype "passive"))
      (node (ref "U1") (pin "R20") (pinfunction "LITCPU_VDD_3_R20") (pintype "passive"))
      (node (ref "U1") (pin "R22") (pinfunction "LITCPU_VDD_7_R22") (pintype "passive"))
      (node (ref "U1") (pin "T20") (pinfunction "LITCPU_VDD_6_T20") (pintype "passive"))
      (node (ref "U1") (pin "T22") (pinfunction "LITCPU_VDD_5_T22") (pintype "passive"))
    )
    (net (code "6") (name "VDD_GPU") (class "Default")
      (node (ref "C4") (pin "2") (pinfunction "2_2") (pintype "passive"))
      (node (ref "C40") (pin "2") (pinfunction "2_2") (pintype "passive"))
      (node (ref "C41") (pin "2") (pinfunction "2_2") (pintype "passive"))
      (node (ref "C42") (pin "2") (pinfunction "2_2") (pintype "passive"))
      (node (ref "C43") (pin "2") (pinfunction "2_2") (pintype "passive"))
      (node (ref "C44") (pin "2") (pinfunction "2_2") (pintype "passive"))
      (node (ref "C45") (pin "2") (pinfunction "2_2") (pintype "passive"))
      (node (ref "C46") (pin "2") (pinfunction "2_2") (pintype "passive"))
      (node (ref "C47") (pin "2") (pinfunction "2_2") (pintype "passive"))
      (node (ref "C48") (pin "2") (pinfunction "2_2") (pintype "passive"))
      (node (ref "C49") (pin "2") (pinfunction "2_2") (pintype "passive"))
      (node (ref "C50") (pin "2") (pinfunction "2_2") (pintype "passive"))
      (node (ref "C51") (pin "2") (pinfunction "2_2") (pintype "passive"))
      (node (ref "C52") (pin "2") (pinfunction "2_2") (pintype "passive"))
      (node (ref "C53") (pin "2") (pinfunction "2_2") (pintype "passive"))
      (node (ref "C54") (pin "2") (pinfunction "2_2") (pintype "passive"))
      (node (ref "C55") (pin "2") (pinfunction "2_2") (pintype "passive"))
      (node (ref "U1") (pin "R11") (pinfunction "GPU_VDD_8_R11") (pintype "passive"))
      (node (ref "U1") (pin "R12") (pinfunction "GPU_VDD_9_R12") (pintype "passive"))
      (node (ref "U1") (pin "R13") (pinfunction "GPU_VDD_13_R13") (pintype "passive"))
      (node (ref "U1") (pin "T11") (pinfunction "GPU_VDD_10_T11") (pintype "passive"))
      (node (ref "U1") (pin "T12") (pinfunction "GPU_VDD_11_T12") (pintype "passive"))
      (node (ref "U1") (pin "T13") (pinfunction "GPU_VDD_12_T13") (pintype "passive"))
      (node (ref "U1") (pin "T14") (pinfunction "GPU_VDD_14_T14") (pintype "passive"))
      (node (ref "U1") (pin "U13") (pinfunction "GPU_VDD_7_U13") (pintype "passive"))
      (node (ref "U1") (pin "V11") (pinfunction "GPU_VDD_15_V11") (pintype "passive"))
      (node (ref "U1") (pin "V12") (pinfunction "GPU_VDD_16_V12") (pintype "passive"))
      (node (ref "U1") (pin "V13") (pinfunction "GPU_VDD_6_V13") (pintype "passive"))
      (node (ref "U1") (pin "V14") (pinfunction "GPU_VDD_5_V14") (pintype "passive"))
      (node (ref "U1") (pin "V15") (pinfunction "GPU_VDD_4_V15") (pintype "passive"))
      (node (ref "U1") (pin "V16") (pinfunction "GPU_VDD_17_V16") (pintype "passive"))
      (node (ref "U1") (pin "W10") (pinfunction "GPU_VDD_20_W10") (pintype "passive"))
      (node (ref "U1") (pin "W11") (pinfunction "GPU_VDD_1_W11") (pintype "passive"))
      (node (ref "U1") (pin "W12") (pinfunction "GPU_VDD_2_W12") (pintype "passive"))
      (node (ref "U1") (pin "W14") (pinfunction "GPU_VDD_3_W14") (pintype "passive"))
      (node (ref "U1") (pin "W15") (pinfunction "GPU_VDD_19_W15") (pintype "passive"))
      (node (ref "U1") (pin "W16") (pinfunction "GPU_VDD_18_W16") (pintype "passive"))
    )
    (net (code "7") (name "VDD_GPU_FB") (class "Default")
      (node (ref "U1") (pin "T15") (pinfunction "GPU_VDD_COM_T15") (pintype "passive"))
    )
    (net (code "8") (name "VDD_LOG") (class "Default")
      (node (ref "C10") (pin "2") (pinfunction "2_2") (pintype "passive"))
      (node (ref "C11") (pin "2") (pinfunction "2_2") (pintype "passive"))
      (node (ref "C12") (pin "2") (pinfunction "2_2") (pintype "passive"))
      (node (ref "C13") (pin "2") (pinfunction "2_2") (pintype "passive"))
      (node (ref "C3") (pin "2") (pinfunction "2_2") (pintype "passive"))
      (node (ref "C6") (pin "2") (pinfunction "2_2") (pintype "passive"))
      (node (ref "C7") (pin "2") (pinfunction "2_2") (pintype "passive"))
      (node (ref "C8") (pin "2") (pinfunction "2_2") (pintype "passive"))
      (node (ref "C9") (pin "2") (pinfunction "2_2") (pintype "passive"))
      (node (ref "U1") (pin "L17") (pinfunction "LOGIC_VDD_10_L17") (pintype "passive"))
      (node (ref "U1") (pin "M17") (pinfunction "LOGIC_VDD_9_M17") (pintype "passive"))
      (node (ref "U1") (pin "T17") (pinfunction "LOGIC_VDD_11_T17") (pintype "passive"))
      (node (ref "U1") (pin "U17") (pinfunction "LOGIC_VDD_8_U17") (pintype "passive"))
      (node (ref "U1") (pin "U18") (pinfunction "LOGIC_VDD_7_U18") (pintype "passive"))
      (node (ref "U1") (pin "U20") (pinfunction "LOGIC_VDD_12_U20") (pintype "passive"))
      (node (ref "U1") (pin "V18") (pinfunction "LOGIC_VDD_5_V18") (pintype "passive"))
      (node (ref "U1") (pin "V19") (pinfunction "LOGIC_VDD_4_V19") (pintype "passive"))
      (node (ref "U1") (pin "V20") (pinfunction "LOGIC_VDD_3_V20") (pintype "passive"))
      (node (ref "U1") (pin "V21") (pinfunction "LOGIC_VDD_2_V21") (pintype "passive"))
      (node (ref "U1") (pin "V22") (pinfunction "LOGIC_VDD_1_V22") (pintype "passive"))
      (node (ref "U1") (pin "W20") (pinfunction "LOGIC_VDD_6_W20") (pintype "passive"))
    )
  )
)
